# Prototyping_OTG_Board.net
KiCad netlist of a schematic drawn in EAGLE
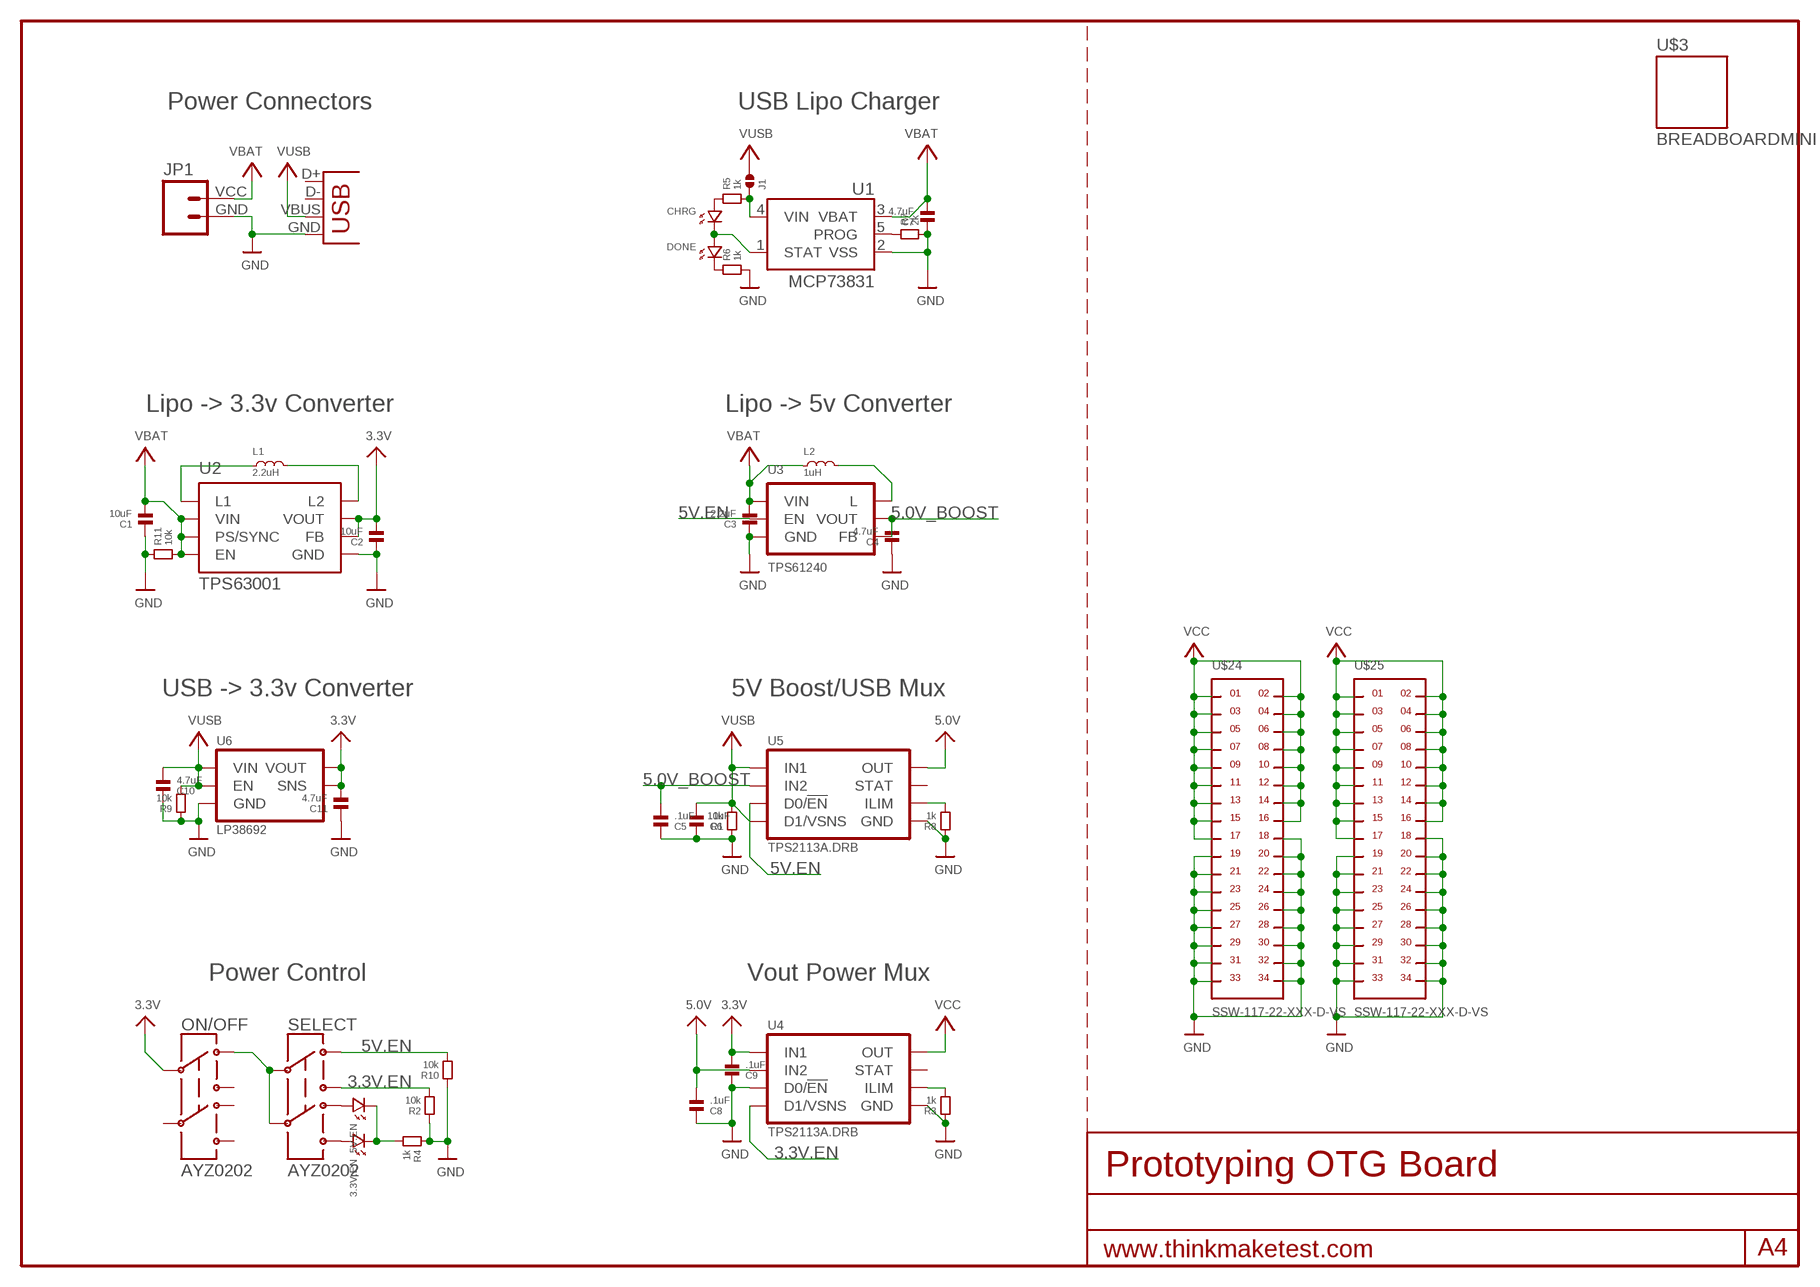
[diagram p0: schematic, sheet 1]

(export (version "E")
  (design (tool "Eeschema 10.0.6"))
  (components
    (comp (ref "3.3V.EN")
      (value "LED.0603")
      (footprint "eagle-import:0603.LED")
      (libsource (lib "eagle-import") (part "LED.0603"))
    )
    (comp (ref "5V.EN")
      (value "LED.0603")
      (footprint "eagle-import:0603.LED")
      (libsource (lib "eagle-import") (part "LED.0603"))
    )
    (comp (ref "C1")
      (value "10uF")
      (footprint "eagle-import:0603")
      (libsource (lib "eagle-import") (part "CAPACITOR.0603"))
    )
    (comp (ref "C2")
      (value "10uF")
      (footprint "eagle-import:0603")
      (libsource (lib "eagle-import") (part "CAPACITOR.0603"))
    )
    (comp (ref "C3")
      (value "2.2uF")
      (footprint "eagle-import:0603")
      (libsource (lib "eagle-import") (part "CAPACITOR.0603"))
    )
    (comp (ref "C4")
      (value "4.7uF")
      (footprint "eagle-import:0603")
      (libsource (lib "eagle-import") (part "CAPACITOR.0603"))
    )
    (comp (ref "C5")
      (value ".1uF")
      (footprint "eagle-import:0603")
      (libsource (lib "eagle-import") (part "CAPACITOR.0603"))
    )
    (comp (ref "C6")
      (value ".1uF")
      (footprint "eagle-import:0603")
      (libsource (lib "eagle-import") (part "CAPACITOR.0603"))
    )
    (comp (ref "C7")
      (value "4.7uF")
      (footprint "eagle-import:0603")
      (libsource (lib "eagle-import") (part "CAPACITOR.0603"))
    )
    (comp (ref "C8")
      (value ".1uF")
      (footprint "eagle-import:0603")
      (libsource (lib "eagle-import") (part "CAPACITOR.0603"))
    )
    (comp (ref "C9")
      (value ".1uF")
      (footprint "eagle-import:0603")
      (libsource (lib "eagle-import") (part "CAPACITOR.0603"))
    )
    (comp (ref "C10")
      (value "4.7uF")
      (footprint "eagle-import:0603")
      (libsource (lib "eagle-import") (part "CAPACITOR.0603"))
    )
    (comp (ref "C11")
      (value "4.7uF")
      (footprint "eagle-import:0603")
      (libsource (lib "eagle-import") (part "CAPACITOR.0603"))
    )
    (comp (ref "CHRG")
      (value "LED.0603")
      (footprint "eagle-import:0603.LED")
      (libsource (lib "eagle-import") (part "LED.0603"))
    )
    (comp (ref "DONE")
      (value "LED.0603")
      (footprint "eagle-import:0603.LED")
      (libsource (lib "eagle-import") (part "LED.0603"))
    )
    (comp (ref "J1")
      (value "SOLDERJUMPER.2.LRG.PASTE")
      (footprint "eagle-import:2.LRG.PASTE")
      (libsource (lib "eagle-import") (part "SOLDERJUMPER.2.LRG.PASTE"))
    )
    (comp (ref "JP1")
      (value "M024UCON-15767")
      (footprint "eagle-import:JST-2-SMD-VERT")
      (libsource (lib "eagle-import") (part "M024UCON-15767"))
    )
    (comp (ref "L1")
      (value "2.2uH")
      (footprint "eagle-import:LQH3NP_M0")
      (libsource (lib "eagle-import") (part "LQH3NPN___MM0"))
    )
    (comp (ref "L2")
      (value "1uH")
      (footprint "eagle-import:0806.(2016)")
      (libsource (lib "eagle-import") (part "MLP2016S1R0M"))
    )
    (comp (ref "ON/OFF")
      (value "AYZ0202")
      (footprint "eagle-import:AYZ0202")
      (libsource (lib "eagle-import") (part "AYZ0202"))
    )
    (comp (ref "R1")
      (value "10k")
      (footprint "eagle-import:0603")
      (libsource (lib "eagle-import") (part "RESISTOR.0603"))
    )
    (comp (ref "R2")
      (value "10k")
      (footprint "eagle-import:0603")
      (libsource (lib "eagle-import") (part "RESISTOR.0603"))
    )
    (comp (ref "R3")
      (value "1k")
      (footprint "eagle-import:0603")
      (libsource (lib "eagle-import") (part "RESISTOR.0603"))
    )
    (comp (ref "R4")
      (value "1k")
      (footprint "eagle-import:0603")
      (libsource (lib "eagle-import") (part "RESISTOR.0603"))
    )
    (comp (ref "R5")
      (value "1k")
      (footprint "eagle-import:0603")
      (libsource (lib "eagle-import") (part "RESISTOR.0603"))
    )
    (comp (ref "R6")
      (value "1k")
      (footprint "eagle-import:0603")
      (libsource (lib "eagle-import") (part "RESISTOR.0603"))
    )
    (comp (ref "R7")
      (value "2k")
      (footprint "eagle-import:0603")
      (libsource (lib "eagle-import") (part "RESISTOR.0603"))
    )
    (comp (ref "R8")
      (value "1k")
      (footprint "eagle-import:0603")
      (libsource (lib "eagle-import") (part "RESISTOR.0603"))
    )
    (comp (ref "R9")
      (value "10k")
      (footprint "eagle-import:0603")
      (libsource (lib "eagle-import") (part "RESISTOR.0603"))
    )
    (comp (ref "R10")
      (value "10k")
      (footprint "eagle-import:0603")
      (libsource (lib "eagle-import") (part "RESISTOR.0603"))
    )
    (comp (ref "R11")
      (value "10k")
      (footprint "eagle-import:0603")
      (libsource (lib "eagle-import") (part "RESISTOR.0603"))
    )
    (comp (ref "SELECT")
      (value "AYZ0202")
      (footprint "eagle-import:AYZ0202")
      (libsource (lib "eagle-import") (part "AYZ0202"))
    )
    (comp (ref "U$3")
      (value "BREADBOARDMINI")
      (footprint "eagle-import:BREADBOARD-MINI")
      (libsource (lib "eagle-import") (part "BREADBOARDMINI"))
    )
    (comp (ref "U$24")
      (value "SSW-117-22-XXX-D-VS")
      (footprint "eagle-import:SSW-117-22-XXX-D-VS")
      (libsource (lib "eagle-import") (part "SSW-117-22-XXX-D-VS"))
    )
    (comp (ref "U$25")
      (value "SSW-117-22-XXX-D-VS")
      (footprint "eagle-import:SSW-117-22-XXX-D-VS")
      (libsource (lib "eagle-import") (part "SSW-117-22-XXX-D-VS"))
    )
    (comp (ref "U1")
      (value "MCP73831")
      (footprint "eagle-import:SOT23-5")
      (libsource (lib "eagle-import") (part "MCP73831"))
    )
    (comp (ref "U2")
      (value "TPS63001")
      (footprint "eagle-import:DRC-S-PVSON-N10")
      (libsource (lib "eagle-import") (part "TPS6300"))
    )
    (comp (ref "U3")
      (value "TPS61240")
      (footprint "eagle-import:DRV")
      (libsource (lib "eagle-import") (part "TPS61240"))
    )
    (comp (ref "U4")
      (value "TPS2113A.DRB")
      (footprint "eagle-import:DRB-S-PVSON-N8")
      (libsource (lib "eagle-import") (part "TPS211XA.DRB"))
    )
    (comp (ref "U5")
      (value "TPS2113A.DRB")
      (footprint "eagle-import:DRB-S-PVSON-N8")
      (libsource (lib "eagle-import") (part "TPS211XA.DRB"))
    )
    (comp (ref "U6")
      (value "LP38692")
      (footprint "eagle-import:LLP6")
      (libsource (lib "eagle-import") (part "LP38692"))
    )
    (comp (ref "X1")
      (value "USBSMD")
      (footprint "eagle-import:USB-MINIB")
      (libsource (lib "eagle-import") (part "USBSMD"))
    )
  )
  (nets
    (net (code "1") (name "/3.3V.EN") (class "Default")
      (node (ref "R2") (pin "2") (pinfunction "2_2") (pintype "bidirectional"))
      (node (ref "SELECT") (pin "1") (pinfunction "3_1") (pintype "bidirectional"))
      (node (ref "U4") (pin "3") (pinfunction "D1/VSNS_3") (pintype "bidirectional"))
    )
    (net (code "2") (name "/5.0V_BOOST") (class "Default")
      (node (ref "C4") (pin "2") (pinfunction "2_2") (pintype "bidirectional"))
      (node (ref "C5") (pin "2") (pinfunction "2_2") (pintype "bidirectional"))
      (node (ref "U3") (pin "2") (pinfunction "VOUT_2") (pintype "bidirectional"))
      (node (ref "U3") (pin "3") (pinfunction "FB_3") (pintype "bidirectional"))
      (node (ref "U5") (pin "6") (pinfunction "IN2_6") (pintype "bidirectional"))
    )
    (net (code "3") (name "/5V.EN") (class "Default")
      (node (ref "R10") (pin "2") (pinfunction "2_2") (pintype "bidirectional"))
      (node (ref "SELECT") (pin "3") (pinfunction "1_3") (pintype "bidirectional"))
      (node (ref "U3") (pin "4") (pinfunction "EN_4") (pintype "bidirectional"))
      (node (ref "U5") (pin "2") (pinfunction "D0/~{EN}_2") (pintype "bidirectional"))
    )
    (net (code "4") (name "3.3V") (class "Default")
      (node (ref "C11") (pin "2") (pinfunction "2_2") (pintype "bidirectional"))
      (node (ref "C2") (pin "2") (pinfunction "2_2") (pintype "bidirectional"))
      (node (ref "C9") (pin "2") (pinfunction "2_2") (pintype "bidirectional"))
      (node (ref "ON/OFF") (pin "2") (pinfunction "2_2") (pintype "bidirectional"))
      (node (ref "U2") (pin "1") (pinfunction "VOUT_1") (pintype "output"))
      (node (ref "U2") (pin "10") (pinfunction "FB_10") (pintype "input"))
      (node (ref "U4") (pin "8") (pinfunction "IN1_8") (pintype "bidirectional"))
      (node (ref "U6") (pin "4") (pinfunction "VOUT_4") (pintype "bidirectional"))
      (node (ref "U6") (pin "5") (pinfunction "SNS_5") (pintype "bidirectional"))
    )
    (net (code "5") (name "5.0V") (class "Default")
      (node (ref "C8") (pin "2") (pinfunction "2_2") (pintype "bidirectional"))
      (node (ref "U4") (pin "6") (pinfunction "IN2_6") (pintype "bidirectional"))
      (node (ref "U5") (pin "7") (pinfunction "OUT_7") (pintype "bidirectional"))
    )
    (net (code "6") (name "GND") (class "Default")
      (node (ref "C1") (pin "1") (pinfunction "1_1") (pintype "bidirectional"))
      (node (ref "C10") (pin "1") (pinfunction "1_1") (pintype "bidirectional"))
      (node (ref "C11") (pin "1") (pinfunction "1_1") (pintype "bidirectional"))
      (node (ref "C2") (pin "1") (pinfunction "1_1") (pintype "bidirectional"))
      (node (ref "C3") (pin "1") (pinfunction "1_1") (pintype "bidirectional"))
      (node (ref "C4") (pin "1") (pinfunction "1_1") (pintype "bidirectional"))
      (node (ref "C5") (pin "1") (pinfunction "1_1") (pintype "bidirectional"))
      (node (ref "C6") (pin "1") (pinfunction "1_1") (pintype "bidirectional"))
      (node (ref "C7") (pin "1") (pinfunction "1_1") (pintype "bidirectional"))
      (node (ref "C8") (pin "1") (pinfunction "1_1") (pintype "bidirectional"))
      (node (ref "C9") (pin "1") (pinfunction "1_1") (pintype "bidirectional"))
      (node (ref "JP1") (pin "GND") (pinfunction "1_GND") (pintype "passive"))
      (node (ref "R1") (pin "1") (pinfunction "1_1") (pintype "bidirectional"))
      (node (ref "R10") (pin "1") (pinfunction "1_1") (pintype "bidirectional"))
      (node (ref "R11") (pin "1") (pinfunction "1_1") (pintype "bidirectional"))
      (node (ref "R2") (pin "1") (pinfunction "1_1") (pintype "bidirectional"))
      (node (ref "R3") (pin "1") (pinfunction "1_1") (pintype "bidirectional"))
      (node (ref "R4") (pin "1") (pinfunction "1_1") (pintype "bidirectional"))
      (node (ref "R6") (pin "2") (pinfunction "2_2") (pintype "bidirectional"))
      (node (ref "R7") (pin "2") (pinfunction "2_2") (pintype "bidirectional"))
      (node (ref "R8") (pin "1") (pinfunction "1_1") (pintype "bidirectional"))
      (node (ref "R9") (pin "1") (pinfunction "1_1") (pintype "bidirectional"))
      (node (ref "U$24") (pin "18") (pinfunction "18_18") (pintype "bidirectional"))
      (node (ref "U$24") (pin "19") (pinfunction "19_19") (pintype "bidirectional"))
      (node (ref "U$24") (pin "20") (pinfunction "20_20") (pintype "bidirectional"))
      (node (ref "U$24") (pin "21") (pinfunction "21_21") (pintype "bidirectional"))
      (node (ref "U$24") (pin "22") (pinfunction "22_22") (pintype "bidirectional"))
      (node (ref "U$24") (pin "23") (pinfunction "23_23") (pintype "bidirectional"))
      (node (ref "U$24") (pin "24") (pinfunction "24_24") (pintype "bidirectional"))
      (node (ref "U$24") (pin "25") (pinfunction "25_25") (pintype "bidirectional"))
      (node (ref "U$24") (pin "26") (pinfunction "26_26") (pintype "bidirectional"))
      (node (ref "U$24") (pin "27") (pinfunction "27_27") (pintype "bidirectional"))
      (node (ref "U$24") (pin "28") (pinfunction "28_28") (pintype "bidirectional"))
      (node (ref "U$24") (pin "29") (pinfunction "29_29") (pintype "bidirectional"))
      (node (ref "U$24") (pin "30") (pinfunction "30_30") (pintype "bidirectional"))
      (node (ref "U$24") (pin "31") (pinfunction "31_31") (pintype "bidirectional"))
      (node (ref "U$24") (pin "32") (pinfunction "32_32") (pintype "bidirectional"))
      (node (ref "U$24") (pin "33") (pinfunction "33_33") (pintype "bidirectional"))
      (node (ref "U$24") (pin "34") (pinfunction "34_34") (pintype "bidirectional"))
      (node (ref "U$25") (pin "18") (pinfunction "18_18") (pintype "bidirectional"))
      (node (ref "U$25") (pin "19") (pinfunction "19_19") (pintype "bidirectional"))
      (node (ref "U$25") (pin "20") (pinfunction "20_20") (pintype "bidirectional"))
      (node (ref "U$25") (pin "21") (pinfunction "21_21") (pintype "bidirectional"))
      (node (ref "U$25") (pin "22") (pinfunction "22_22") (pintype "bidirectional"))
      (node (ref "U$25") (pin "23") (pinfunction "23_23") (pintype "bidirectional"))
      (node (ref "U$25") (pin "24") (pinfunction "24_24") (pintype "bidirectional"))
      (node (ref "U$25") (pin "25") (pinfunction "25_25") (pintype "bidirectional"))
      (node (ref "U$25") (pin "26") (pinfunction "26_26") (pintype "bidirectional"))
      (node (ref "U$25") (pin "27") (pinfunction "27_27") (pintype "bidirectional"))
      (node (ref "U$25") (pin "28") (pinfunction "28_28") (pintype "bidirectional"))
      (node (ref "U$25") (pin "29") (pinfunction "29_29") (pintype "bidirectional"))
      (node (ref "U$25") (pin "30") (pinfunction "30_30") (pintype "bidirectional"))
      (node (ref "U$25") (pin "31") (pinfunction "31_31") (pintype "bidirectional"))
      (node (ref "U$25") (pin "32") (pinfunction "32_32") (pintype "bidirectional"))
      (node (ref "U$25") (pin "33") (pinfunction "33_33") (pintype "bidirectional"))
      (node (ref "U$25") (pin "34") (pinfunction "34_34") (pintype "bidirectional"))
      (node (ref "U1") (pin "2") (pinfunction "VSS_2") (pintype "power_in"))
      (node (ref "U2") (pin "3") (pinfunction "GND_3") (pintype "power_in"))
      (node (ref "U2") (pin "9") (pinfunction "GND_9") (pintype "power_in"))
      (node (ref "U2") (pin "TH") (pinfunction "GND_TH") (pintype "power_in"))
      (node (ref "U2") (pin "TH@1") (pinfunction "GND_TH@1") (pintype "power_in"))
      (node (ref "U2") (pin "TH@2") (pinfunction "GND_TH@2") (pintype "power_in"))
      (node (ref "U3") (pin "1") (pinfunction "GND_1") (pintype "bidirectional"))
      (node (ref "U3") (pin "PAD") (pinfunction "GND_PAD") (pintype "bidirectional"))
      (node (ref "U4") (pin "2") (pinfunction "D0/~{EN}_2") (pintype "bidirectional"))
      (node (ref "U4") (pin "5") (pinfunction "GND_5") (pintype "bidirectional"))
      (node (ref "U4") (pin "TH") (pinfunction "GND_TH") (pintype "bidirectional"))
      (node (ref "U4") (pin "TH@1") (pinfunction "GND_TH@1") (pintype "bidirectional"))
      (node (ref "U4") (pin "TH@2") (pinfunction "GND_TH@2") (pintype "bidirectional"))
      (node (ref "U5") (pin "5") (pinfunction "GND_5") (pintype "bidirectional"))
      (node (ref "U5") (pin "TH") (pinfunction "GND_TH") (pintype "bidirectional"))
      (node (ref "U5") (pin "TH@1") (pinfunction "GND_TH@1") (pintype "bidirectional"))
      (node (ref "U5") (pin "TH@2") (pinfunction "GND_TH@2") (pintype "bidirectional"))
      (node (ref "U6") (pin "2") (pinfunction "GND_2") (pintype "bidirectional"))
      (node (ref "U6") (pin "PAD") (pinfunction "GND_PAD") (pintype "bidirectional"))
      (node (ref "X1") (pin "GND") (pinfunction "GND_GND") (pintype "bidirectional"))
    )
    (net (code "7") (name "Net-(3.3V.EN-1)") (class "Default")
      (node (ref "3.3V.EN") (pin "P$1") (pinfunction "1_P$1") (pintype "bidirectional"))
      (node (ref "SELECT") (pin "4") (pinfunction "6_4") (pintype "bidirectional"))
    )
    (net (code "8") (name "Net-(3.3V.EN-2)") (class "Default")
      (node (ref "3.3V.EN") (pin "P$2") (pinfunction "2_P$2") (pintype "bidirectional"))
      (node (ref "5V.EN") (pin "P$2") (pinfunction "2_P$2") (pintype "bidirectional"))
      (node (ref "R4") (pin "2") (pinfunction "2_2") (pintype "bidirectional"))
    )
    (net (code "9") (name "Net-(5V.EN-1)") (class "Default")
      (node (ref "5V.EN") (pin "P$1") (pinfunction "1_P$1") (pintype "bidirectional"))
      (node (ref "SELECT") (pin "6") (pinfunction "4_6") (pintype "bidirectional"))
    )
    (net (code "10") (name "Net-(CHRG-1)") (class "Default")
      (node (ref "CHRG") (pin "P$1") (pinfunction "1_P$1") (pintype "bidirectional"))
      (node (ref "R5") (pin "1") (pinfunction "1_1") (pintype "bidirectional"))
    )
    (net (code "11") (name "Net-(CHRG-2)") (class "Default")
      (node (ref "CHRG") (pin "P$2") (pinfunction "2_P$2") (pintype "bidirectional"))
      (node (ref "DONE") (pin "P$1") (pinfunction "1_P$1") (pintype "bidirectional"))
      (node (ref "U1") (pin "1") (pinfunction "STAT_1") (pintype "output"))
    )
    (net (code "12") (name "Net-(DONE-2)") (class "Default")
      (node (ref "DONE") (pin "P$2") (pinfunction "2_P$2") (pintype "bidirectional"))
      (node (ref "R6") (pin "1") (pinfunction "1_1") (pintype "bidirectional"))
    )
    (net (code "13") (name "Net-(ON/OFF-1)") (class "Default")
      (node (ref "ON/OFF") (pin "3") (pinfunction "1_3") (pintype "bidirectional"))
      (node (ref "SELECT") (pin "2") (pinfunction "2_2") (pintype "bidirectional"))
      (node (ref "SELECT") (pin "5") (pinfunction "5_5") (pintype "bidirectional"))
    )
    (net (code "14") (name "Net-(U1-PROG)") (class "Default")
      (node (ref "R7") (pin "1") (pinfunction "1_1") (pintype "bidirectional"))
      (node (ref "U1") (pin "5") (pinfunction "PROG_5") (pintype "input"))
    )
    (net (code "15") (name "Net-(U1-VIN)") (class "Default")
      (node (ref "J1") (pin "1") (pinfunction "1_1") (pintype "bidirectional"))
      (node (ref "R5") (pin "2") (pinfunction "2_2") (pintype "bidirectional"))
      (node (ref "U1") (pin "4") (pinfunction "VIN_4") (pintype "power_in"))
    )
    (net (code "16") (name "Net-(U2-L1)") (class "Default")
      (node (ref "L1") (pin "1") (pinfunction "1_1") (pintype "passive"))
      (node (ref "U2") (pin "4") (pinfunction "L1_4") (pintype "passive"))
    )
    (net (code "17") (name "Net-(U2-L2)") (class "Default")
      (node (ref "L1") (pin "2") (pinfunction "2_2") (pintype "passive"))
      (node (ref "U2") (pin "2") (pinfunction "L2_2") (pintype "passive"))
    )
    (net (code "18") (name "Net-(U3-L)") (class "Default")
      (node (ref "L2") (pin "2") (pinfunction "2_2") (pintype "passive"))
      (node (ref "U3") (pin "5") (pinfunction "L_5") (pintype "bidirectional"))
    )
    (net (code "19") (name "Net-(U4-ILIM)") (class "Default")
      (node (ref "R3") (pin "2") (pinfunction "2_2") (pintype "bidirectional"))
      (node (ref "U4") (pin "4") (pinfunction "ILIM_4") (pintype "bidirectional"))
    )
    (net (code "20") (name "Net-(U5-ILIM)") (class "Default")
      (node (ref "R8") (pin "2") (pinfunction "2_2") (pintype "bidirectional"))
      (node (ref "U5") (pin "4") (pinfunction "ILIM_4") (pintype "bidirectional"))
    )
    (net (code "21") (name "VBAT") (class "Default")
      (node (ref "C1") (pin "2") (pinfunction "2_2") (pintype "bidirectional"))
      (node (ref "C3") (pin "2") (pinfunction "2_2") (pintype "bidirectional"))
      (node (ref "C7") (pin "2") (pinfunction "2_2") (pintype "bidirectional"))
      (node (ref "JP1") (pin "VCC") (pinfunction "2_VCC") (pintype "passive"))
      (node (ref "L2") (pin "1") (pinfunction "1_1") (pintype "passive"))
      (node (ref "R11") (pin "2") (pinfunction "2_2") (pintype "bidirectional"))
      (node (ref "U1") (pin "3") (pinfunction "VBAT_3") (pintype "power_in"))
      (node (ref "U2") (pin "5") (pinfunction "VIN_5") (pintype "input"))
      (node (ref "U2") (pin "6") (pinfunction "EN_6") (pintype "input"))
      (node (ref "U2") (pin "7") (pinfunction "PS/SYNC_7") (pintype "input"))
      (node (ref "U2") (pin "8") (pinfunction "VIN_8") (pintype "input"))
      (node (ref "U3") (pin "6") (pinfunction "VIN_6") (pintype "bidirectional"))
    )
    (net (code "22") (name "VCC") (class "Default")
      (node (ref "U$24") (pin "1") (pinfunction "1_1") (pintype "bidirectional"))
      (node (ref "U$24") (pin "10") (pinfunction "10_10") (pintype "bidirectional"))
      (node (ref "U$24") (pin "11") (pinfunction "11_11") (pintype "bidirectional"))
      (node (ref "U$24") (pin "12") (pinfunction "12_12") (pintype "bidirectional"))
      (node (ref "U$24") (pin "13") (pinfunction "13_13") (pintype "bidirectional"))
      (node (ref "U$24") (pin "14") (pinfunction "14_14") (pintype "bidirectional"))
      (node (ref "U$24") (pin "15") (pinfunction "15_15") (pintype "bidirectional"))
      (node (ref "U$24") (pin "16") (pinfunction "16_16") (pintype "bidirectional"))
      (node (ref "U$24") (pin "17") (pinfunction "17_17") (pintype "bidirectional"))
      (node (ref "U$24") (pin "2") (pinfunction "2_2") (pintype "bidirectional"))
      (node (ref "U$24") (pin "3") (pinfunction "3_3") (pintype "bidirectional"))
      (node (ref "U$24") (pin "4") (pinfunction "4_4") (pintype "bidirectional"))
      (node (ref "U$24") (pin "5") (pinfunction "5_5") (pintype "bidirectional"))
      (node (ref "U$24") (pin "6") (pinfunction "6_6") (pintype "bidirectional"))
      (node (ref "U$24") (pin "7") (pinfunction "7_7") (pintype "bidirectional"))
      (node (ref "U$24") (pin "8") (pinfunction "8_8") (pintype "bidirectional"))
      (node (ref "U$24") (pin "9") (pinfunction "9_9") (pintype "bidirectional"))
      (node (ref "U$25") (pin "1") (pinfunction "1_1") (pintype "bidirectional"))
      (node (ref "U$25") (pin "10") (pinfunction "10_10") (pintype "bidirectional"))
      (node (ref "U$25") (pin "11") (pinfunction "11_11") (pintype "bidirectional"))
      (node (ref "U$25") (pin "12") (pinfunction "12_12") (pintype "bidirectional"))
      (node (ref "U$25") (pin "13") (pinfunction "13_13") (pintype "bidirectional"))
      (node (ref "U$25") (pin "14") (pinfunction "14_14") (pintype "bidirectional"))
      (node (ref "U$25") (pin "15") (pinfunction "15_15") (pintype "bidirectional"))
      (node (ref "U$25") (pin "16") (pinfunction "16_16") (pintype "bidirectional"))
      (node (ref "U$25") (pin "17") (pinfunction "17_17") (pintype "bidirectional"))
      (node (ref "U$25") (pin "2") (pinfunction "2_2") (pintype "bidirectional"))
      (node (ref "U$25") (pin "3") (pinfunction "3_3") (pintype "bidirectional"))
      (node (ref "U$25") (pin "4") (pinfunction "4_4") (pintype "bidirectional"))
      (node (ref "U$25") (pin "5") (pinfunction "5_5") (pintype "bidirectional"))
      (node (ref "U$25") (pin "6") (pinfunction "6_6") (pintype "bidirectional"))
      (node (ref "U$25") (pin "7") (pinfunction "7_7") (pintype "bidirectional"))
      (node (ref "U$25") (pin "8") (pinfunction "8_8") (pintype "bidirectional"))
      (node (ref "U$25") (pin "9") (pinfunction "9_9") (pintype "bidirectional"))
      (node (ref "U4") (pin "7") (pinfunction "OUT_7") (pintype "bidirectional"))
    )
    (net (code "23") (name "VUSB") (class "Default")
      (node (ref "C10") (pin "2") (pinfunction "2_2") (pintype "bidirectional"))
      (node (ref "C6") (pin "2") (pinfunction "2_2") (pintype "bidirectional"))
      (node (ref "J1") (pin "2") (pinfunction "2_2") (pintype "bidirectional"))
      (node (ref "R1") (pin "2") (pinfunction "2_2") (pintype "bidirectional"))
      (node (ref "R9") (pin "2") (pinfunction "2_2") (pintype "bidirectional"))
      (node (ref "U5") (pin "3") (pinfunction "D1/VSNS_3") (pintype "bidirectional"))
      (node (ref "U5") (pin "8") (pinfunction "IN1_8") (pintype "bidirectional"))
      (node (ref "U6") (pin "1") (pinfunction "VIN_1") (pintype "bidirectional"))
      (node (ref "U6") (pin "3") (pinfunction "EN_3") (pintype "bidirectional"))
      (node (ref "U6") (pin "6") (pinfunction "VIN_6") (pintype "bidirectional"))
      (node (ref "X1") (pin "VBUS") (pinfunction "VBUS_VBUS") (pintype "bidirectional"))
    )
    (net (code "24") (name "unconnected-(ON/OFF-3-Pad1)") (class "Default")
      (node (ref "ON/OFF") (pin "1") (pinfunction "3_1") (pintype "bidirectional"))
    )
    (net (code "25") (name "unconnected-(ON/OFF-4-Pad6)") (class "Default")
      (node (ref "ON/OFF") (pin "6") (pinfunction "4_6") (pintype "bidirectional"))
    )
    (net (code "26") (name "unconnected-(ON/OFF-6-Pad4)") (class "Default")
      (node (ref "ON/OFF") (pin "4") (pinfunction "6_4") (pintype "bidirectional"))
    )
    (net (code "27") (name "unconnected-(ON/OFF-Pad5)") (class "Default")
      (node (ref "ON/OFF") (pin "5") (pinfunction "5_5") (pintype "bidirectional"))
    )
    (net (code "28") (name "unconnected-(U4-STAT-Pad1)") (class "Default")
      (node (ref "U4") (pin "1") (pinfunction "STAT_1") (pintype "bidirectional"))
    )
    (net (code "29") (name "unconnected-(U5-STAT-Pad1)") (class "Default")
      (node (ref "U5") (pin "1") (pinfunction "STAT_1") (pintype "bidirectional"))
    )
    (net (code "30") (name "unconnected-(X1-PadD+)") (class "Default")
      (node (ref "X1") (pin "D+") (pinfunction "D+_D+") (pintype "bidirectional"))
    )
    (net (code "31") (name "unconnected-(X1-PadD-)") (class "Default")
      (node (ref "X1") (pin "D-") (pinfunction "D-_D-") (pintype "bidirectional"))
    )
  )
)
